# HM_RETI_Ambilight_v1_0.net
KiCad netlist of a schematic drawn in Altium Designer
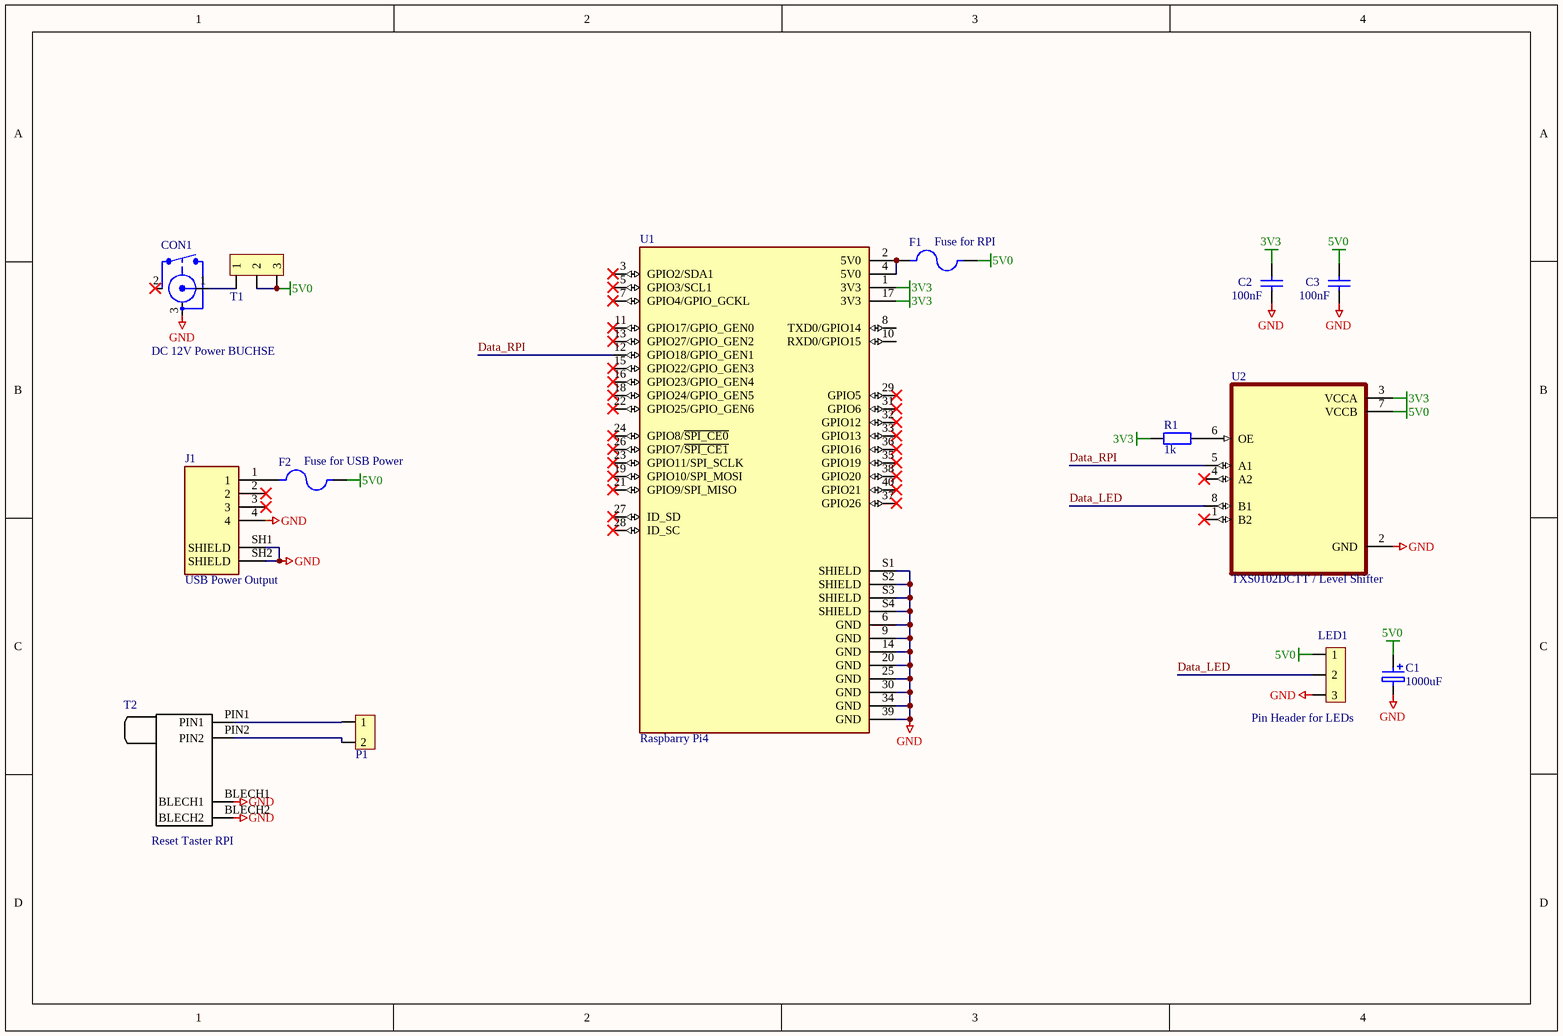
[diagram p0: HM_RETI_Ambilight_v1_0.SchDoc]

(export (version "E")
  (design (tool "Eeschema 10.0.6"))
  (components
    (comp (ref "C1")
      (value "1000uF")
      (footprint "C_10mm_left")
      (description "C, SMD, ELKO, 6,5V, ± 10%")
      (libsource (lib "philipp") (part "C ELKO"))
    )
    (comp (ref "C2")
      (value "100nF")
      (footprint "C_0603")
      (description "C, SMD, MLCC, 25V, ± 10%")
      (libsource (lib "philipp") (part "C SMD"))
    )
    (comp (ref "C3")
      (value "100nF")
      (footprint "C_0603")
      (description "C, SMD, MLCC, 25V, ± 10%")
      (libsource (lib "philipp") (part "C SMD"))
    )
    (comp (ref "CON1")
      (value "DC 12V Power BUCHSE")
      (footprint "DC_BUCHSE_LUMBERG_2_35mm_STIFT")
      (description "DC_BUCHSE_LUMBERG_2_35mm_STIFT")
      (libsource (lib "basti") (part "DC_BUCHSE_LUMBERG_2_35mm_STIFT"))
    )
    (comp (ref "F1")
      (value "Fuse for RPI")
      (footprint "FUSER_MF-MSMF250/16X-2")
      (description "Polymeric PTC Resettable Fuse 16V 2.5 A Ih Surface Mount 1812 (4532 Metric), Concave")
      (fields (field (name "MP") "MF-MSMF250/16X-2") (field (name "MF") "Bourns"))
      (libsource (lib "basti") (part "MF-MSMF250/16X-2"))
    )
    (comp (ref "F2")
      (value "Fuse for USB Power")
      (footprint "FUSER_MF-MSMF250/16X-2")
      (description "Polymeric PTC Resettable Fuse 16V 1.1 A Ih Surface Mount 1812 (4532 Metric), Concave")
      (fields (field (name "MP") "MF-MSMF110/16-2") (field (name "MF") "Bourns"))
      (libsource (lib "basti") (part "MF-MSMF250/16X-2"))
    )
    (comp (ref "J1")
      (value "USB Power Output")
      (footprint "CUI_UJ2-AH-4-TH")
      (description "Type A, USB 2.0, 1 A, Right Angle, Through Hole, USB Receptacle")
      (fields (field (name "MF") "CUI Devices") (field (name "DIGI-KEY_PART_NUMBER") "102-3994-ND"))
      (libsource (lib "basti") (part "UJ2-AH-4-TH"))
    )
    (comp (ref "LED1")
      (value "Pin Header for LEDs")
      (footprint "Header 3x1")
      (description "Board-to-Board-Steckverbinder, vertikal, 2.54 mm, 3 Kontakt(e), Stiftleiste, Baureihe WR-PHD")
      (libsource (lib "basti") (part "Pin Header 3x1"))
    )
    (comp (ref "P1")
      (value "Pin Header 2x1")
      (footprint "Header 2x1")
      (description "Board-to-Board-Steckverbinder, vertikal, 2.54 mm, 2 Kontakt(e), Stiftleiste, Baureihe WR-PHD")
      (libsource (lib "basti") (part "Pin Header 2x1"))
    )
    (comp (ref "R1")
      (value "1k")
      (footprint "R_0603")
      (description "R, SMD, Chip, 100mW, ± 1%")
      (libsource (lib "philipp") (part "R SMD"))
    )
    (comp (ref "T1")
      (value "Pin Header 3x1")
      (footprint "Header 3x1")
      (description "Board-to-Board-Steckverbinder, vertikal, 2.54 mm, 3 Kontakt(e), Stiftleiste, Baureihe WR-PHD")
      (libsource (lib "") (part "Pin Header 3x1_1"))
    )
    (comp (ref "T2")
      (value "Reset Taster RPI")
      (footprint "431256058736")
      (description "Taster, THT, 90°, 8,35mm, black")
      (libsource (lib "basti") (part "TASTER_RESET"))
    )
    (comp (ref "U1")
      (value "Raspbarry Pi4")
      (footprint "MODULE_RASPBERRY_PI_3_MODEL_B+")
      (description "BCM2835 Raspberry Pi Model B+ - ARM11, VideoCore MPU Embedded Evaluation Board")
      (fields (field (name "MP") "RASPBERRY_PI_3_MODEL_B+"))
      (libsource (lib "basti") (part "RASPBERRY_PI_3_MODEL_B+"))
    )
    (comp (ref "U2")
      (value "TXS0102DCTT / Level Shifter")
      (footprint "SOP65P400X130-8N")
      (description "2-Bit Bidirectional Voltage-Level Shifter for Open-Drain and Push-Pull Application")
      (fields (field (name "MP") "TXS0102DCTT") (field (name "MF") "Texas Instruments"))
      (libsource (lib "basti") (part "TXS0102DCTT"))
    )
  )
  (nets
    (net (code "1") (name "/Data_LED") (class "Default")
      (node (ref "LED1") (pin "2") (pinfunction "2_2") (pintype "passive"))
      (node (ref "U2") (pin "8") (pinfunction "B1_8") (pintype "bidirectional"))
    )
    (net (code "2") (name "/Data_RPI") (class "Default")
      (node (ref "U1") (pin "12") (pinfunction "GPIO18/GPIO_GEN1_12") (pintype "bidirectional"))
      (node (ref "U2") (pin "5") (pinfunction "A1_5") (pintype "bidirectional"))
    )
    (net (code "3") (name "3V3") (class "Default")
      (node (ref "C2") (pin "1") (pinfunction "1_1") (pintype "passive"))
      (node (ref "R1") (pin "1") (pinfunction "1_1") (pintype "passive"))
      (node (ref "U1") (pin "1") (pinfunction "3V3_1") (pintype "power_in"))
      (node (ref "U1") (pin "17") (pinfunction "3V3_17") (pintype "power_in"))
      (node (ref "U2") (pin "3") (pinfunction "VCCA_3") (pintype "power_in"))
    )
    (net (code "4") (name "5V0") (class "Default")
      (node (ref "C1") (pin "1") (pinfunction "1_1") (pintype "passive"))
      (node (ref "C3") (pin "1") (pinfunction "1_1") (pintype "passive"))
      (node (ref "F1") (pin "2") (pinfunction "2_2") (pintype "passive"))
      (node (ref "F2") (pin "2") (pinfunction "2_2") (pintype "passive"))
      (node (ref "LED1") (pin "1") (pinfunction "1_1") (pintype "passive"))
      (node (ref "T1") (pin "2") (pinfunction "2_2") (pintype "passive"))
      (node (ref "T1") (pin "3") (pinfunction "3_3") (pintype "passive"))
      (node (ref "U2") (pin "7") (pinfunction "VCCB_7") (pintype "power_in"))
    )
    (net (code "5") (name "GND") (class "Default")
      (node (ref "C1") (pin "2") (pinfunction "2_2") (pintype "passive"))
      (node (ref "C2") (pin "2") (pinfunction "2_2") (pintype "passive"))
      (node (ref "C3") (pin "2") (pinfunction "2_2") (pintype "passive"))
      (node (ref "CON1") (pin "3") (pinfunction "A_3") (pintype "passive"))
      (node (ref "J1") (pin "4") (pinfunction "4_4") (pintype "passive"))
      (node (ref "J1") (pin "SH1") (pinfunction "SHIELD_SH1") (pintype "passive"))
      (node (ref "J1") (pin "SH2") (pinfunction "SHIELD_SH2") (pintype "passive"))
      (node (ref "LED1") (pin "3") (pinfunction "3_3") (pintype "passive"))
      (node (ref "T2") (pin "BLECH1") (pinfunction "BLECH1_BLECH1") (pintype "passive"))
      (node (ref "T2") (pin "BLECH2") (pinfunction "BLECH2_BLECH2") (pintype "passive"))
      (node (ref "U1") (pin "14") (pinfunction "GND_14") (pintype "power_in"))
      (node (ref "U1") (pin "20") (pinfunction "GND_20") (pintype "power_in"))
      (node (ref "U1") (pin "25") (pinfunction "GND_25") (pintype "power_in"))
      (node (ref "U1") (pin "30") (pinfunction "GND_30") (pintype "power_in"))
      (node (ref "U1") (pin "34") (pinfunction "GND_34") (pintype "power_in"))
      (node (ref "U1") (pin "39") (pinfunction "GND_39") (pintype "power_in"))
      (node (ref "U1") (pin "6") (pinfunction "GND_6") (pintype "power_in"))
      (node (ref "U1") (pin "9") (pinfunction "GND_9") (pintype "power_in"))
      (node (ref "U1") (pin "S1") (pinfunction "SHIELD_S1") (pintype "power_in"))
      (node (ref "U1") (pin "S2") (pinfunction "SHIELD_S2") (pintype "power_in"))
      (node (ref "U1") (pin "S3") (pinfunction "SHIELD_S3") (pintype "power_in"))
      (node (ref "U1") (pin "S4") (pinfunction "SHIELD_S4") (pintype "power_in"))
      (node (ref "U2") (pin "2") (pinfunction "GND_2") (pintype "power_in"))
    )
    (net (code "6") (name "Net-(CON1-I)") (class "Default")
      (node (ref "CON1") (pin "1") (pinfunction "I_1") (pintype "passive"))
      (node (ref "T1") (pin "1") (pinfunction "1_1") (pintype "passive"))
    )
    (net (code "7") (name "Net-(F1-Pad1)") (class "Default")
      (node (ref "F1") (pin "1") (pinfunction "1_1") (pintype "passive"))
      (node (ref "U1") (pin "2") (pinfunction "5V0_2") (pintype "power_in"))
      (node (ref "U1") (pin "4") (pinfunction "5V0_4") (pintype "power_in"))
    )
    (net (code "8") (name "Net-(F2-Pad1)") (class "Default")
      (node (ref "F2") (pin "1") (pinfunction "1_1") (pintype "passive"))
      (node (ref "J1") (pin "1") (pinfunction "1_1") (pintype "passive"))
    )
    (net (code "9") (name "Net-(P1-Pad1)") (class "Default")
      (node (ref "P1") (pin "1") (pinfunction "1_1") (pintype "passive"))
      (node (ref "T2") (pin "PIN1") (pinfunction "PIN1_PIN1") (pintype "passive"))
    )
    (net (code "10") (name "Net-(P1-Pad2)") (class "Default")
      (node (ref "P1") (pin "2") (pinfunction "2_2") (pintype "passive"))
      (node (ref "T2") (pin "PIN2") (pinfunction "PIN2_PIN2") (pintype "passive"))
    )
    (net (code "11") (name "Net-(U2-OE)") (class "Default")
      (node (ref "R1") (pin "2") (pinfunction "2_2") (pintype "passive"))
      (node (ref "U2") (pin "6") (pinfunction "OE_6") (pintype "input"))
    )
    (net (code "12") (name "unconnected-(CON1-SW-Pad2)") (class "Default")
      (node (ref "CON1") (pin "2") (pinfunction "SW_2") (pintype "passive+no_connect"))
    )
    (net (code "13") (name "unconnected-(J1-Pad2)") (class "Default")
      (node (ref "J1") (pin "2") (pinfunction "2_2") (pintype "passive+no_connect"))
    )
    (net (code "14") (name "unconnected-(J1-Pad3)") (class "Default")
      (node (ref "J1") (pin "3") (pinfunction "3_3") (pintype "passive+no_connect"))
    )
    (net (code "15") (name "unconnected-(U1-GPIO2{slash}SDA1-Pad3)") (class "Default")
      (node (ref "U1") (pin "3") (pinfunction "GPIO2/SDA1_3") (pintype "bidirectional+no_connect"))
    )
    (net (code "16") (name "unconnected-(U1-GPIO3{slash}SCL1-Pad5)") (class "Default")
      (node (ref "U1") (pin "5") (pinfunction "GPIO3/SCL1_5") (pintype "bidirectional+no_connect"))
    )
    (net (code "17") (name "unconnected-(U1-GPIO4{slash}GPIO_GCKL-Pad7)") (class "Default")
      (node (ref "U1") (pin "7") (pinfunction "GPIO4/GPIO_GCKL_7") (pintype "bidirectional+no_connect"))
    )
    (net (code "18") (name "unconnected-(U1-GPIO5-Pad29)") (class "Default")
      (node (ref "U1") (pin "29") (pinfunction "GPIO5_29") (pintype "bidirectional+no_connect"))
    )
    (net (code "19") (name "unconnected-(U1-GPIO6-Pad31)") (class "Default")
      (node (ref "U1") (pin "31") (pinfunction "GPIO6_31") (pintype "bidirectional+no_connect"))
    )
    (net (code "20") (name "unconnected-(U1-GPIO7{slash}~{SPI_CE1}-Pad26)") (class "Default")
      (node (ref "U1") (pin "26") (pinfunction "GPIO7/~{SPI_CE1}_26") (pintype "bidirectional+no_connect"))
    )
    (net (code "21") (name "unconnected-(U1-GPIO8{slash}~{SPI_CE0}-Pad24)") (class "Default")
      (node (ref "U1") (pin "24") (pinfunction "GPIO8/~{SPI_CE0}_24") (pintype "bidirectional+no_connect"))
    )
    (net (code "22") (name "unconnected-(U1-GPIO9{slash}SPI_MISO-Pad21)") (class "Default")
      (node (ref "U1") (pin "21") (pinfunction "GPIO9/SPI_MISO_21") (pintype "bidirectional+no_connect"))
    )
    (net (code "23") (name "unconnected-(U1-GPIO10{slash}SPI_MOSI-Pad19)") (class "Default")
      (node (ref "U1") (pin "19") (pinfunction "GPIO10/SPI_MOSI_19") (pintype "bidirectional+no_connect"))
    )
    (net (code "24") (name "unconnected-(U1-GPIO11{slash}SPI_SCLK-Pad23)") (class "Default")
      (node (ref "U1") (pin "23") (pinfunction "GPIO11/SPI_SCLK_23") (pintype "bidirectional+no_connect"))
    )
    (net (code "25") (name "unconnected-(U1-GPIO12-Pad32)") (class "Default")
      (node (ref "U1") (pin "32") (pinfunction "GPIO12_32") (pintype "bidirectional+no_connect"))
    )
    (net (code "26") (name "unconnected-(U1-GPIO13-Pad33)") (class "Default")
      (node (ref "U1") (pin "33") (pinfunction "GPIO13_33") (pintype "bidirectional+no_connect"))
    )
    (net (code "27") (name "unconnected-(U1-GPIO16-Pad36)") (class "Default")
      (node (ref "U1") (pin "36") (pinfunction "GPIO16_36") (pintype "bidirectional+no_connect"))
    )
    (net (code "28") (name "unconnected-(U1-GPIO17{slash}GPIO_GEN0-Pad11)") (class "Default")
      (node (ref "U1") (pin "11") (pinfunction "GPIO17/GPIO_GEN0_11") (pintype "bidirectional+no_connect"))
    )
    (net (code "29") (name "unconnected-(U1-GPIO19-Pad35)") (class "Default")
      (node (ref "U1") (pin "35") (pinfunction "GPIO19_35") (pintype "bidirectional+no_connect"))
    )
    (net (code "30") (name "unconnected-(U1-GPIO20-Pad38)") (class "Default")
      (node (ref "U1") (pin "38") (pinfunction "GPIO20_38") (pintype "bidirectional+no_connect"))
    )
    (net (code "31") (name "unconnected-(U1-GPIO21-Pad40)") (class "Default")
      (node (ref "U1") (pin "40") (pinfunction "GPIO21_40") (pintype "bidirectional+no_connect"))
    )
    (net (code "32") (name "unconnected-(U1-GPIO22{slash}GPIO_GEN3-Pad15)") (class "Default")
      (node (ref "U1") (pin "15") (pinfunction "GPIO22/GPIO_GEN3_15") (pintype "bidirectional+no_connect"))
    )
    (net (code "33") (name "unconnected-(U1-GPIO23{slash}GPIO_GEN4-Pad16)") (class "Default")
      (node (ref "U1") (pin "16") (pinfunction "GPIO23/GPIO_GEN4_16") (pintype "bidirectional+no_connect"))
    )
    (net (code "34") (name "unconnected-(U1-GPIO24{slash}GPIO_GEN5-Pad18)") (class "Default")
      (node (ref "U1") (pin "18") (pinfunction "GPIO24/GPIO_GEN5_18") (pintype "bidirectional+no_connect"))
    )
    (net (code "35") (name "unconnected-(U1-GPIO25{slash}GPIO_GEN6-Pad22)") (class "Default")
      (node (ref "U1") (pin "22") (pinfunction "GPIO25/GPIO_GEN6_22") (pintype "bidirectional+no_connect"))
    )
    (net (code "36") (name "unconnected-(U1-GPIO26-Pad37)") (class "Default")
      (node (ref "U1") (pin "37") (pinfunction "GPIO26_37") (pintype "bidirectional+no_connect"))
    )
    (net (code "37") (name "unconnected-(U1-GPIO27{slash}GPIO_GEN2-Pad13)") (class "Default")
      (node (ref "U1") (pin "13") (pinfunction "GPIO27/GPIO_GEN2_13") (pintype "bidirectional+no_connect"))
    )
    (net (code "38") (name "unconnected-(U1-ID_SC-Pad28)") (class "Default")
      (node (ref "U1") (pin "28") (pinfunction "ID_SC_28") (pintype "bidirectional+no_connect"))
    )
    (net (code "39") (name "unconnected-(U1-ID_SD-Pad27)") (class "Default")
      (node (ref "U1") (pin "27") (pinfunction "ID_SD_27") (pintype "bidirectional+no_connect"))
    )
    (net (code "40") (name "unconnected-(U1-RXD0{slash}GPIO15-Pad10)") (class "Default")
      (node (ref "U1") (pin "10") (pinfunction "RXD0/GPIO15_10") (pintype "bidirectional"))
    )
    (net (code "41") (name "unconnected-(U1-TXD0{slash}GPIO14-Pad8)") (class "Default")
      (node (ref "U1") (pin "8") (pinfunction "TXD0/GPIO14_8") (pintype "bidirectional"))
    )
    (net (code "42") (name "unconnected-(U2-A2-Pad4)") (class "Default")
      (node (ref "U2") (pin "4") (pinfunction "A2_4") (pintype "bidirectional+no_connect"))
    )
    (net (code "43") (name "unconnected-(U2-B2-Pad1)") (class "Default")
      (node (ref "U2") (pin "1") (pinfunction "B2_1") (pintype "bidirectional+no_connect"))
    )
  )
)
